# PWR_TPS7A8300.net
KiCad netlist of a schematic drawn in Altium Designer
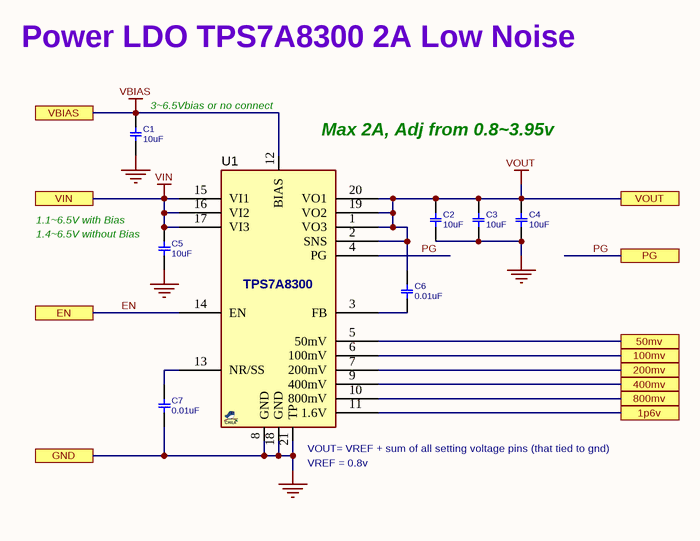
[diagram p0: PWR_TPS7A8300.SchDoc]

(export (version "E")
  (design (tool "Eeschema 10.0.6"))
  (components
    (comp (ref "C1")
      (value "10uF")
      (footprint "C0402")
      (description "CAP, MLCC")
      (libsource (lib "mlcc_smd_passive") (part "CAP_SMD_MLCC_100n50T"))
    )
    (comp (ref "C2")
      (value "10uF")
      (footprint "C0402")
      (description "CAP, MLCC")
      (libsource (lib "mlcc_smd_passive") (part "CAP_SMD_MLCC_100n50T"))
    )
    (comp (ref "C3")
      (value "10uF")
      (footprint "C0402")
      (description "CAP, MLCC")
      (libsource (lib "mlcc_smd_passive") (part "CAP_SMD_MLCC_100n50T"))
    )
    (comp (ref "C4")
      (value "10uF")
      (footprint "C0402")
      (description "CAP, MLCC")
      (libsource (lib "mlcc_smd_passive") (part "CAP_SMD_MLCC_100n50T"))
    )
    (comp (ref "C5")
      (value "10uF")
      (footprint "C0402")
      (description "CAP, MLCC")
      (libsource (lib "mlcc_smd_passive") (part "CAP_SMD_MLCC_100n50T"))
    )
    (comp (ref "C6")
      (value "0.01uF")
      (footprint "C0402")
      (description "CAP, MLCC")
      (fields (field (name "MANF_P#") "MANF_PART#") (field (name "MANF") "Murata"))
      (libsource (lib "passive_smd") (part "CAP_SMD_MLCC"))
    )
    (comp (ref "C7")
      (value "0.01uF")
      (footprint "C0402")
      (description "CAP, MLCC")
      (fields (field (name "MANF_P#") "MANF_PART#") (field (name "MANF") "Murata"))
      (libsource (lib "passive_smd") (part "CAP_SMD_MLCC"))
    )
    (comp (ref "U1")
      (value "TPS7A8300")
      (footprint "QFN65_20T")
      (description "REG, Linear, LDO0.12V, 2A, QFN-20")
      (fields (field (name "MANF") "Texas Instruments") (field (name "MANF_P#") "TPS7A8300RGW"))
      (libsource (lib "pwr_reg_linear_LDO_highPSRR") (part "VREG_TPS7A8300_QFN20"))
    )
  )
  (nets
    (net (code "1") (name "/1p6v") (class "Default")
      (node (ref "U1") (pin "11") (pinfunction "1.6V_11") (pintype "passive"))
    )
    (net (code "2") (name "/50mv") (class "Default")
      (node (ref "U1") (pin "5") (pinfunction "50mV_5") (pintype "passive"))
    )
    (net (code "3") (name "/100mv") (class "Default")
      (node (ref "U1") (pin "6") (pinfunction "100mV_6") (pintype "passive"))
    )
    (net (code "4") (name "/200mv") (class "Default")
      (node (ref "U1") (pin "7") (pinfunction "200mV_7") (pintype "passive"))
    )
    (net (code "5") (name "/400mv") (class "Default")
      (node (ref "U1") (pin "9") (pinfunction "400mV_9") (pintype "passive"))
    )
    (net (code "6") (name "/800mv") (class "Default")
      (node (ref "U1") (pin "10") (pinfunction "800mV_10") (pintype "passive"))
    )
    (net (code "7") (name "/EN") (class "Default")
      (node (ref "U1") (pin "14") (pinfunction "EN_14") (pintype "passive"))
    )
    (net (code "8") (name "/PG") (class "Default")
      (node (ref "U1") (pin "4") (pinfunction "PG_4") (pintype "passive"))
    )
    (net (code "9") (name "GND") (class "Default")
      (node (ref "C1") (pin "2") (pinfunction "2_2") (pintype "passive"))
      (node (ref "C2") (pin "2") (pinfunction "2_2") (pintype "passive"))
      (node (ref "C3") (pin "2") (pinfunction "2_2") (pintype "passive"))
      (node (ref "C4") (pin "2") (pinfunction "2_2") (pintype "passive"))
      (node (ref "C5") (pin "2") (pinfunction "2_2") (pintype "passive"))
      (node (ref "C7") (pin "2") (pinfunction "2_2") (pintype "passive"))
      (node (ref "U1") (pin "18") (pinfunction "GND_18") (pintype "power_in"))
      (node (ref "U1") (pin "21") (pinfunction "TP_21") (pintype "passive"))
      (node (ref "U1") (pin "8") (pinfunction "GND_8") (pintype "power_in"))
    )
    (net (code "10") (name "Net-(U1-FB)") (class "Default")
      (node (ref "C6") (pin "2") (pinfunction "2_2") (pintype "passive"))
      (node (ref "U1") (pin "3") (pinfunction "FB_3") (pintype "passive"))
    )
    (net (code "11") (name "Net-(U1-NR{slash}SS)") (class "Default")
      (node (ref "C7") (pin "1") (pinfunction "1_1") (pintype "passive"))
      (node (ref "U1") (pin "13") (pinfunction "NR/SS_13") (pintype "passive"))
    )
    (net (code "12") (name "VBIAS") (class "Default")
      (node (ref "C1") (pin "1") (pinfunction "1_1") (pintype "passive"))
      (node (ref "U1") (pin "12") (pinfunction "BIAS_12") (pintype "passive"))
    )
    (net (code "13") (name "VIN") (class "Default")
      (node (ref "C5") (pin "1") (pinfunction "1_1") (pintype "passive"))
      (node (ref "U1") (pin "15") (pinfunction "VI1_15") (pintype "power_in"))
      (node (ref "U1") (pin "16") (pinfunction "VI2_16") (pintype "power_in"))
      (node (ref "U1") (pin "17") (pinfunction "VI3_17") (pintype "power_in"))
    )
    (net (code "14") (name "VOUT") (class "Default")
      (node (ref "C2") (pin "1") (pinfunction "1_1") (pintype "passive"))
      (node (ref "C3") (pin "1") (pinfunction "1_1") (pintype "passive"))
      (node (ref "C4") (pin "1") (pinfunction "1_1") (pintype "passive"))
      (node (ref "C6") (pin "1") (pinfunction "1_1") (pintype "passive"))
      (node (ref "U1") (pin "1") (pinfunction "VO3_1") (pintype "power_in"))
      (node (ref "U1") (pin "19") (pinfunction "VO2_19") (pintype "power_in"))
      (node (ref "U1") (pin "2") (pinfunction "SNS_2") (pintype "passive"))
      (node (ref "U1") (pin "20") (pinfunction "VO1_20") (pintype "power_in"))
    )
  )
)
